# C172-XPNDR-v001.net
KiCad netlist of a schematic drawn in EasyEDA
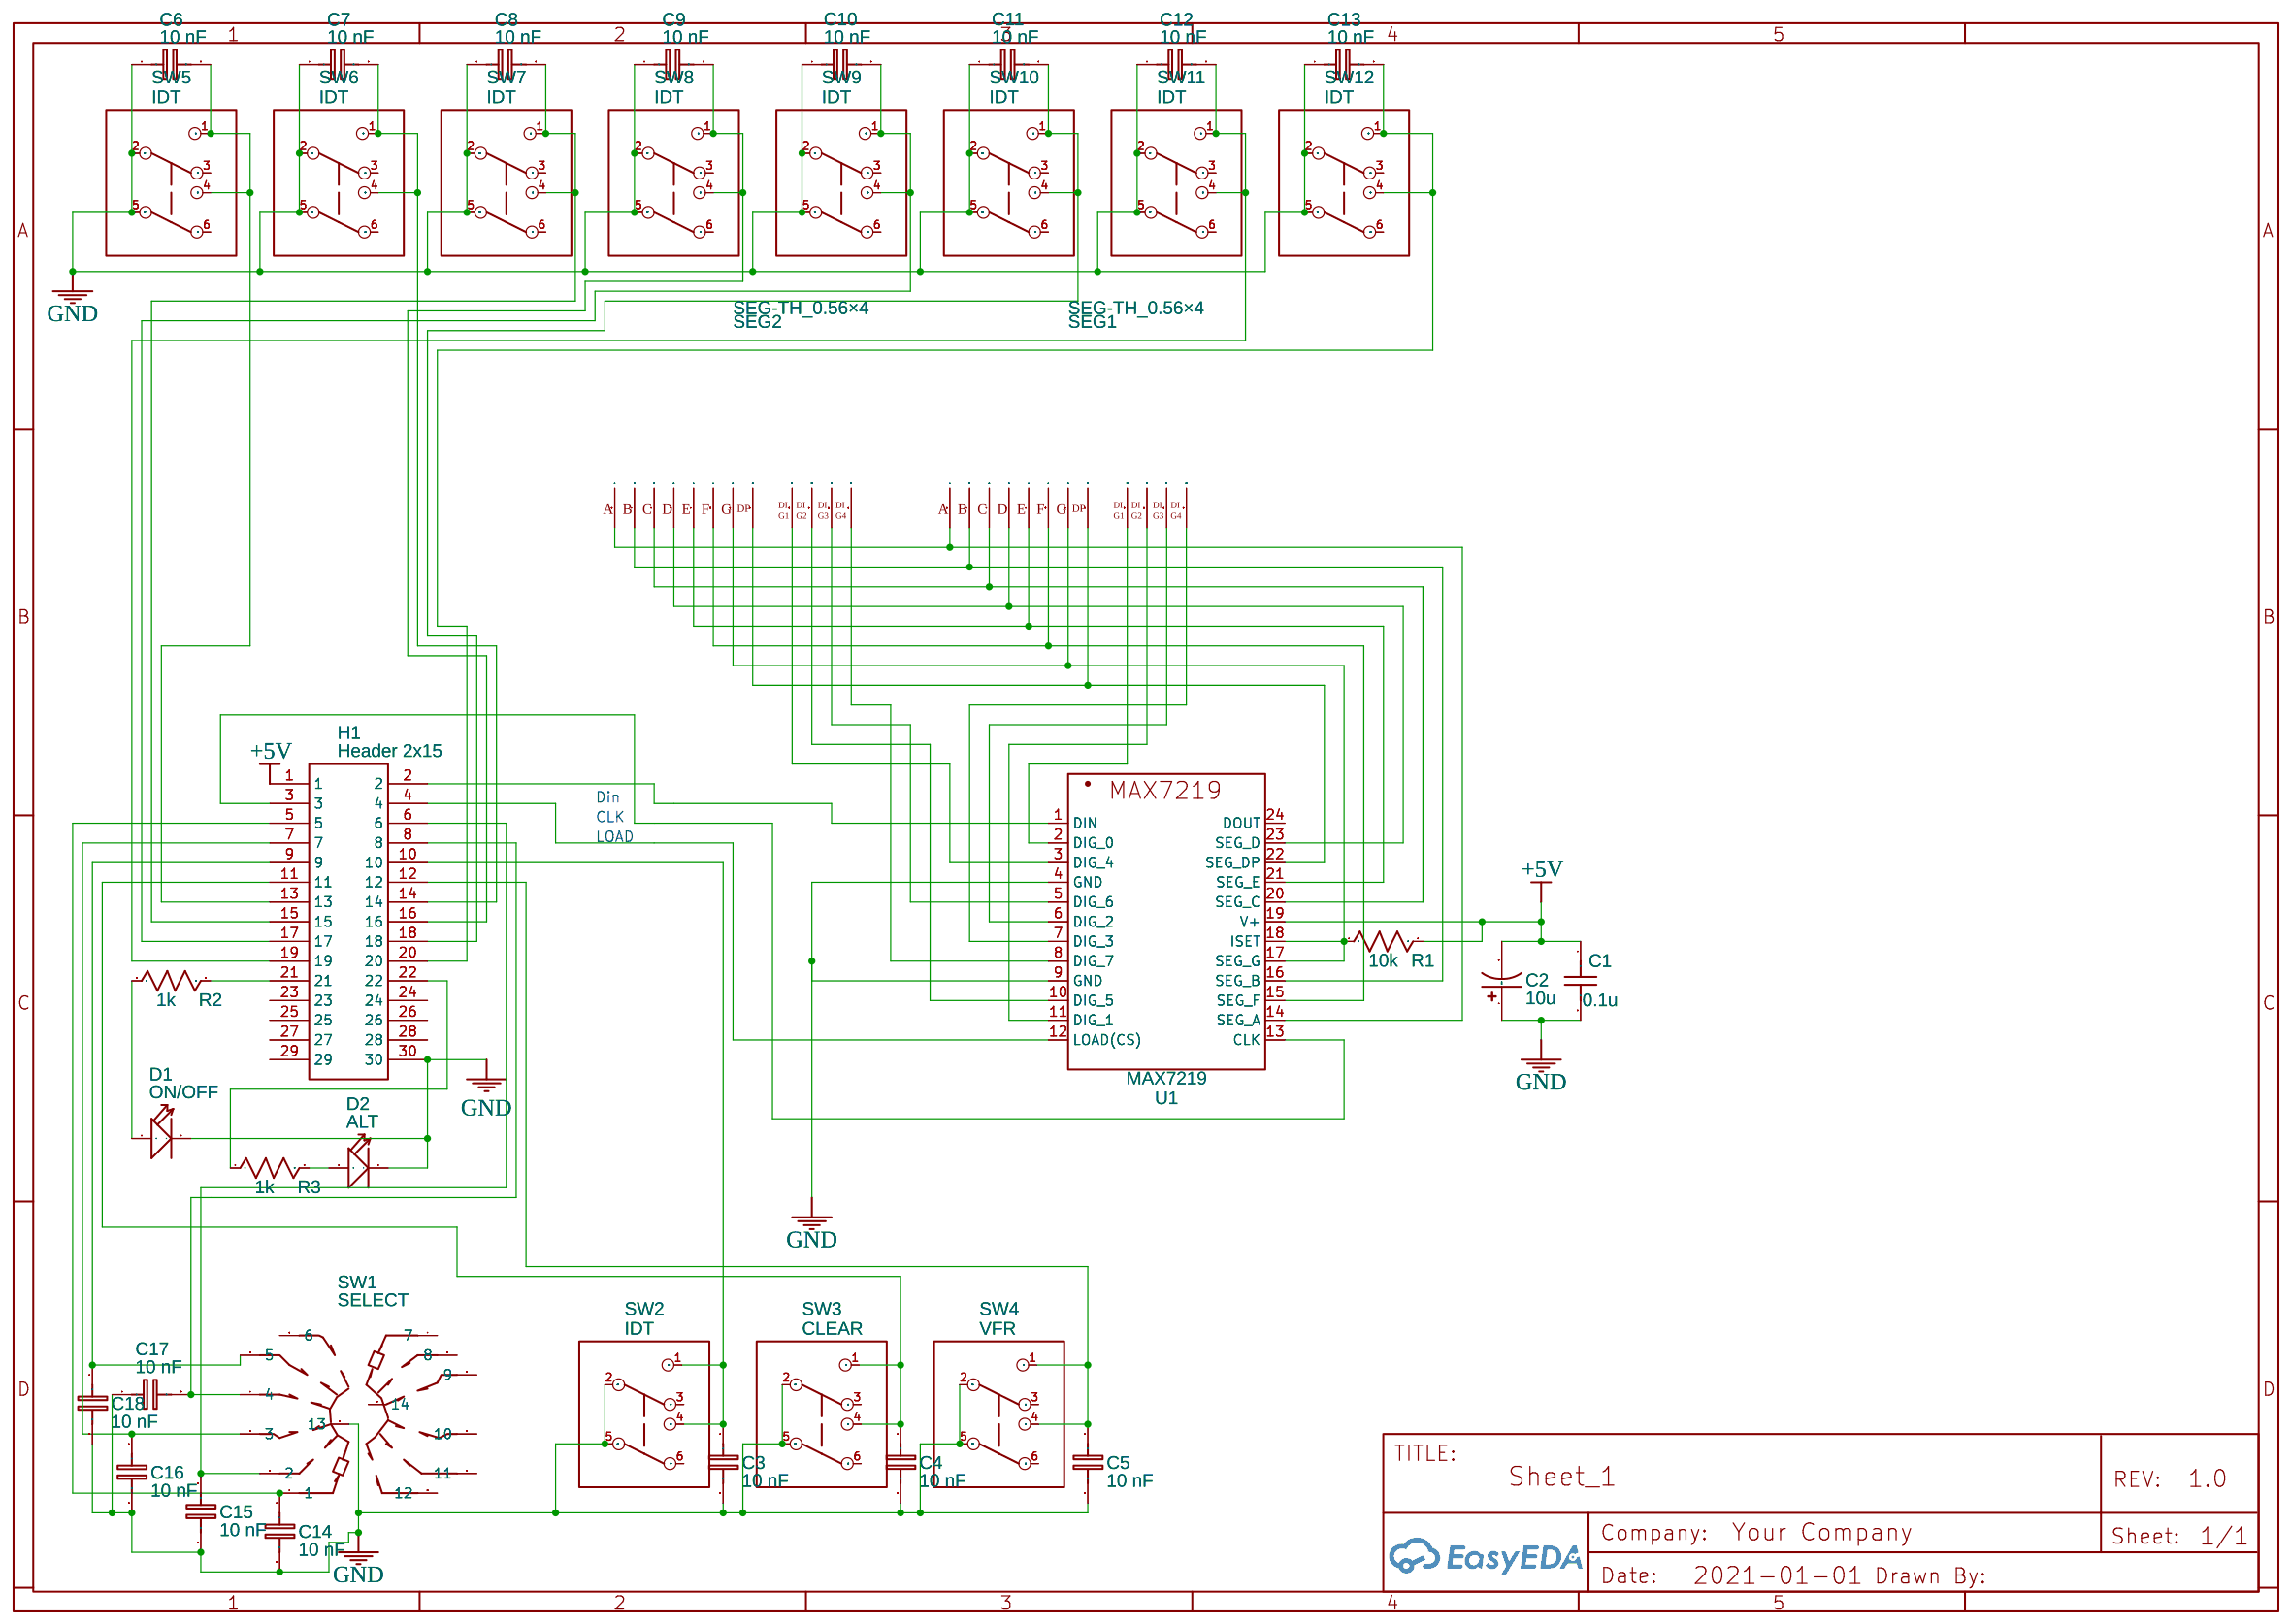
[diagram p0: schematic sheet]

(export (version "E")
  (design (tool "Eeschema 10.0.6"))
  (components
    (comp (ref "C1") (value "0.1u") (libsource (lib "") (part "C_0201_US")))
    (comp (ref "C2") (value "10u") (libsource (lib "") (part "C_Tan_SMD_A_US")))
    (comp (ref "C3") (value "10 nF") (libsource (lib "") (part "Capacitor1_EU_2")))
    (comp (ref "C4") (value "10 nF") (libsource (lib "") (part "Capacitor1_EU_2")))
    (comp (ref "C5") (value "10 nF") (libsource (lib "") (part "Capacitor1_EU")))
    (comp (ref "C6") (value "10 nF") (libsource (lib "") (part "Capacitor1_EU_3")))
    (comp (ref "C7") (value "10 nF") (libsource (lib "") (part "Capacitor1_EU_1")))
    (comp (ref "C8") (value "10 nF") (libsource (lib "") (part "Capacitor1_EU_1")))
    (comp (ref "C9") (value "10 nF") (libsource (lib "") (part "Capacitor1_EU_1")))
    (comp (ref "C10") (value "10 nF") (libsource (lib "") (part "Capacitor1_EU_1")))
    (comp (ref "C11") (value "10 nF") (libsource (lib "") (part "Capacitor1_EU_1")))
    (comp (ref "C12") (value "10 nF") (libsource (lib "") (part "Capacitor1_EU_3")))
    (comp (ref "C13") (value "10 nF") (libsource (lib "") (part "Capacitor1_EU_3")))
    (comp (ref "C14") (value "10 nF") (libsource (lib "") (part "Capacitor1_EU")))
    (comp (ref "C15") (value "10 nF") (libsource (lib "") (part "Capacitor1_EU")))
    (comp (ref "C16") (value "10 nF") (libsource (lib "") (part "Capacitor1_EU")))
    (comp (ref "C17") (value "10 nF") (libsource (lib "") (part "Capacitor1_EU_3")))
    (comp (ref "C18") (value "10 nF") (libsource (lib "") (part "Capacitor1_EU")))
    (comp (ref "D1")
      (value "ON/OFF")
      (fields (field (name "BOM_Manufacturer Part") "?"))
      (libsource (lib "") (part "DIP LED Red-Red;"))
    )
    (comp (ref "D2")
      (value "ALT")
      (fields (field (name "BOM_Manufacturer Part") "?"))
      (libsource (lib "") (part "DIP LED Red-Red;"))
    )
    (comp (ref "H1") (value "Header 2x15") (libsource (lib "") (part "Header 2x15")))
    (comp (ref "R1") (value "10k") (libsource (lib "") (part "R_0201_US")))
    (comp (ref "R2") (value "1k") (libsource (lib "") (part "R_0201_US")))
    (comp (ref "R3") (value "1k") (libsource (lib "") (part "R_0201_US")))
    (comp (ref "SEG1")
      (value "SEG-TH_0.56×4")
      (fields (field (name "BOM_Supplier Part") "C109200"))
      (libsource (lib "") (part "SEG-TH_0.56×4"))
    )
    (comp (ref "SEG2")
      (value "SEG-TH_0.56×4")
      (fields (field (name "BOM_Supplier Part") "C109200"))
      (libsource (lib "") (part "SEG-TH_0.56×4"))
    )
    (comp (ref "SW1")
      (value "SELECT")
      (fields (field (name "BOM_Manufacturer Part") "CK1060"))
      (libsource (lib "") (part "LORLIN  2P6T PCB SW"))
    )
    (comp (ref "SW2") (value "IDT") (libsource (lib "") (part "SW_PUSH_DPDT_MINI_7x7")))
    (comp (ref "SW3") (value "CLEAR") (libsource (lib "") (part "SW_PUSH_DPDT_MINI_7x7")))
    (comp (ref "SW4") (value "VFR") (libsource (lib "") (part "SW_PUSH_DPDT_MINI_7x7")))
    (comp (ref "SW5") (value "IDT") (libsource (lib "") (part "SW_PUSH_DPDT_MINI_7x7")))
    (comp (ref "SW6") (value "IDT") (libsource (lib "") (part "SW_PUSH_DPDT_MINI_7x7")))
    (comp (ref "SW7") (value "IDT") (libsource (lib "") (part "SW_PUSH_DPDT_MINI_7x7")))
    (comp (ref "SW8") (value "IDT") (libsource (lib "") (part "SW_PUSH_DPDT_MINI_7x7")))
    (comp (ref "SW9") (value "IDT") (libsource (lib "") (part "SW_PUSH_DPDT_MINI_7x7")))
    (comp (ref "SW10") (value "IDT") (libsource (lib "") (part "SW_PUSH_DPDT_MINI_7x7")))
    (comp (ref "SW11") (value "IDT") (libsource (lib "") (part "SW_PUSH_DPDT_MINI_7x7")))
    (comp (ref "SW12") (value "IDT") (libsource (lib "") (part "SW_PUSH_DPDT_MINI_7x7")))
    (comp (ref "U1")
      (value "MAX7219")
      (fields (field (name "BOM_Manufacturer Part") "MAXIM") (field (name "BOM_Supplier Part") "C129565"))
      (libsource (lib "") (part "MAX7219"))
    )
  )
  (nets
    (net (code "1") (name "+5V") (class "Default")
      (node (ref "C1") (pin "1") (pinfunction "1_1") (pintype "unspecified"))
      (node (ref "C2") (pin "2") (pinfunction "2_2") (pintype "unspecified"))
      (node (ref "H1") (pin "1") (pinfunction "1_1") (pintype "unspecified"))
      (node (ref "R1") (pin "2") (pinfunction "2_2") (pintype "unspecified"))
      (node (ref "U1") (pin "19") (pinfunction "V+_19") (pintype "unspecified"))
    )
    (net (code "2") (name "GND") (class "Default")
      (node (ref "C1") (pin "2") (pinfunction "2_2") (pintype "unspecified"))
      (node (ref "C10") (pin "1") (pinfunction "1_1") (pintype "unspecified"))
      (node (ref "C11") (pin "1") (pinfunction "1_1") (pintype "unspecified"))
      (node (ref "C12") (pin "1") (pinfunction "1_1") (pintype "unspecified"))
      (node (ref "C13") (pin "1") (pinfunction "1_1") (pintype "unspecified"))
      (node (ref "C14") (pin "2") (pinfunction "2_2") (pintype "unspecified"))
      (node (ref "C15") (pin "2") (pinfunction "2_2") (pintype "unspecified"))
      (node (ref "C16") (pin "2") (pinfunction "2_2") (pintype "unspecified"))
      (node (ref "C17") (pin "1") (pinfunction "1_1") (pintype "unspecified"))
      (node (ref "C18") (pin "2") (pinfunction "2_2") (pintype "unspecified"))
      (node (ref "C2") (pin "1") (pinfunction "1_1") (pintype "unspecified"))
      (node (ref "C3") (pin "2") (pinfunction "2_2") (pintype "unspecified"))
      (node (ref "C4") (pin "2") (pinfunction "2_2") (pintype "unspecified"))
      (node (ref "C5") (pin "2") (pinfunction "2_2") (pintype "unspecified"))
      (node (ref "C6") (pin "1") (pinfunction "1_1") (pintype "unspecified"))
      (node (ref "C7") (pin "1") (pinfunction "1_1") (pintype "unspecified"))
      (node (ref "C8") (pin "1") (pinfunction "1_1") (pintype "unspecified"))
      (node (ref "C9") (pin "1") (pinfunction "1_1") (pintype "unspecified"))
      (node (ref "D1") (pin "K") (pinfunction "-_K") (pintype "unspecified"))
      (node (ref "D2") (pin "K") (pinfunction "-_K") (pintype "unspecified"))
      (node (ref "H1") (pin "30") (pinfunction "30_30") (pintype "unspecified"))
      (node (ref "SW1") (pin "13") (pinfunction "13_13") (pintype "unspecified"))
      (node (ref "SW10") (pin "2") (pinfunction "COM1_2") (pintype "unspecified"))
      (node (ref "SW10") (pin "5") (pinfunction "COM2_5") (pintype "unspecified"))
      (node (ref "SW11") (pin "2") (pinfunction "COM1_2") (pintype "unspecified"))
      (node (ref "SW11") (pin "5") (pinfunction "COM2_5") (pintype "unspecified"))
      (node (ref "SW12") (pin "2") (pinfunction "COM1_2") (pintype "unspecified"))
      (node (ref "SW12") (pin "5") (pinfunction "COM2_5") (pintype "unspecified"))
      (node (ref "SW2") (pin "2") (pinfunction "COM1_2") (pintype "unspecified"))
      (node (ref "SW2") (pin "5") (pinfunction "COM2_5") (pintype "unspecified"))
      (node (ref "SW3") (pin "2") (pinfunction "COM1_2") (pintype "unspecified"))
      (node (ref "SW3") (pin "5") (pinfunction "COM2_5") (pintype "unspecified"))
      (node (ref "SW4") (pin "2") (pinfunction "COM1_2") (pintype "unspecified"))
      (node (ref "SW4") (pin "5") (pinfunction "COM2_5") (pintype "unspecified"))
      (node (ref "SW5") (pin "2") (pinfunction "COM1_2") (pintype "unspecified"))
      (node (ref "SW5") (pin "5") (pinfunction "COM2_5") (pintype "unspecified"))
      (node (ref "SW6") (pin "2") (pinfunction "COM1_2") (pintype "unspecified"))
      (node (ref "SW6") (pin "5") (pinfunction "COM2_5") (pintype "unspecified"))
      (node (ref "SW7") (pin "2") (pinfunction "COM1_2") (pintype "unspecified"))
      (node (ref "SW7") (pin "5") (pinfunction "COM2_5") (pintype "unspecified"))
      (node (ref "SW8") (pin "2") (pinfunction "COM1_2") (pintype "unspecified"))
      (node (ref "SW8") (pin "5") (pinfunction "COM2_5") (pintype "unspecified"))
      (node (ref "SW9") (pin "2") (pinfunction "COM1_2") (pintype "unspecified"))
      (node (ref "SW9") (pin "5") (pinfunction "COM2_5") (pintype "unspecified"))
      (node (ref "U1") (pin "4") (pinfunction "GND_4") (pintype "unspecified"))
      (node (ref "U1") (pin "9") (pinfunction "GND_9") (pintype "unspecified"))
    )
    (net (code "3") (name "Net-(C14-Pad1)") (class "Default")
      (node (ref "C14") (pin "1") (pinfunction "1_1") (pintype "unspecified"))
      (node (ref "H1") (pin "5") (pinfunction "5_5") (pintype "unspecified"))
      (node (ref "SW1") (pin "1") (pinfunction "1_1") (pintype "unspecified"))
    )
    (net (code "4") (name "Net-(C15-Pad1)") (class "Default")
      (node (ref "C15") (pin "1") (pinfunction "1_1") (pintype "unspecified"))
      (node (ref "H1") (pin "6") (pinfunction "6_6") (pintype "unspecified"))
      (node (ref "SW1") (pin "2") (pinfunction "2_2") (pintype "unspecified"))
    )
    (net (code "5") (name "Net-(C16-Pad1)") (class "Default")
      (node (ref "C16") (pin "1") (pinfunction "1_1") (pintype "unspecified"))
      (node (ref "H1") (pin "7") (pinfunction "7_7") (pintype "unspecified"))
      (node (ref "SW1") (pin "3") (pinfunction "3_3") (pintype "unspecified"))
    )
    (net (code "6") (name "Net-(C17-Pad2)") (class "Default")
      (node (ref "C17") (pin "2") (pinfunction "2_2") (pintype "unspecified"))
      (node (ref "H1") (pin "8") (pinfunction "8_8") (pintype "unspecified"))
      (node (ref "SW1") (pin "4") (pinfunction "4_4") (pintype "unspecified"))
    )
    (net (code "7") (name "Net-(C18-Pad1)") (class "Default")
      (node (ref "C18") (pin "1") (pinfunction "1_1") (pintype "unspecified"))
      (node (ref "H1") (pin "9") (pinfunction "9_9") (pintype "unspecified"))
      (node (ref "SW1") (pin "5") (pinfunction "5_5") (pintype "unspecified"))
    )
    (net (code "8") (name "Net-(D1-+)") (class "Default")
      (node (ref "D1") (pin "A") (pinfunction "+_A") (pintype "unspecified"))
      (node (ref "R2") (pin "1") (pinfunction "1_1") (pintype "unspecified"))
    )
    (net (code "9") (name "Net-(D2-+)") (class "Default")
      (node (ref "D2") (pin "A") (pinfunction "+_A") (pintype "unspecified"))
      (node (ref "R3") (pin "2") (pinfunction "2_2") (pintype "unspecified"))
    )
    (net (code "10") (name "Net-(H1-Pad21)") (class "Default")
      (node (ref "H1") (pin "21") (pinfunction "21_21") (pintype "unspecified"))
      (node (ref "R2") (pin "2") (pinfunction "2_2") (pintype "unspecified"))
    )
    (net (code "11") (name "Net-(H1-Pad22)") (class "Default")
      (node (ref "H1") (pin "22") (pinfunction "22_22") (pintype "unspecified"))
      (node (ref "R3") (pin "1") (pinfunction "1_1") (pintype "unspecified"))
    )
    (net (code "12") (name "Net-(SEG1-A)") (class "Default")
      (node (ref "SEG1") (pin "11") (pinfunction "A_11") (pintype "input"))
      (node (ref "SEG2") (pin "11") (pinfunction "A_11") (pintype "input"))
      (node (ref "U1") (pin "14") (pinfunction "SEG_A_14") (pintype "unspecified"))
    )
    (net (code "13") (name "Net-(SEG1-B)") (class "Default")
      (node (ref "SEG1") (pin "7") (pinfunction "B_7") (pintype "input"))
      (node (ref "SEG2") (pin "7") (pinfunction "B_7") (pintype "input"))
      (node (ref "U1") (pin "16") (pinfunction "SEG_B_16") (pintype "unspecified"))
    )
    (net (code "14") (name "Net-(SEG1-C)") (class "Default")
      (node (ref "SEG1") (pin "4") (pinfunction "C_4") (pintype "input"))
      (node (ref "SEG2") (pin "4") (pinfunction "C_4") (pintype "input"))
      (node (ref "U1") (pin "20") (pinfunction "SEG_C_20") (pintype "unspecified"))
    )
    (net (code "15") (name "Net-(SEG1-D)") (class "Default")
      (node (ref "SEG1") (pin "2") (pinfunction "D_2") (pintype "input"))
      (node (ref "SEG2") (pin "2") (pinfunction "D_2") (pintype "input"))
      (node (ref "U1") (pin "23") (pinfunction "SEG_D_23") (pintype "unspecified"))
    )
    (net (code "16") (name "Net-(SEG1-DIG1)") (class "Default")
      (node (ref "SEG1") (pin "12") (pinfunction "DIG1_12") (pintype "input"))
      (node (ref "U1") (pin "2") (pinfunction "DIG_0_2") (pintype "unspecified"))
    )
    (net (code "17") (name "Net-(SEG1-DIG2)") (class "Default")
      (node (ref "SEG1") (pin "9") (pinfunction "DIG2_9") (pintype "input"))
      (node (ref "U1") (pin "11") (pinfunction "DIG_1_11") (pintype "unspecified"))
    )
    (net (code "18") (name "Net-(SEG1-DIG3)") (class "Default")
      (node (ref "SEG1") (pin "8") (pinfunction "DIG3_8") (pintype "input"))
      (node (ref "U1") (pin "6") (pinfunction "DIG_2_6") (pintype "unspecified"))
    )
    (net (code "19") (name "Net-(SEG1-DIG4)") (class "Default")
      (node (ref "SEG1") (pin "6") (pinfunction "DIG4_6") (pintype "input"))
      (node (ref "U1") (pin "7") (pinfunction "DIG_3_7") (pintype "unspecified"))
    )
    (net (code "20") (name "Net-(SEG1-DP)") (class "Default")
      (node (ref "SEG1") (pin "3") (pinfunction "DP_3") (pintype "input"))
      (node (ref "SEG2") (pin "3") (pinfunction "DP_3") (pintype "input"))
      (node (ref "U1") (pin "22") (pinfunction "SEG_DP_22") (pintype "unspecified"))
    )
    (net (code "21") (name "Net-(SEG1-E)") (class "Default")
      (node (ref "SEG1") (pin "1") (pinfunction "E_1") (pintype "input"))
      (node (ref "SEG2") (pin "1") (pinfunction "E_1") (pintype "input"))
      (node (ref "U1") (pin "21") (pinfunction "SEG_E_21") (pintype "unspecified"))
    )
    (net (code "22") (name "Net-(SEG1-F)") (class "Default")
      (node (ref "SEG1") (pin "10") (pinfunction "F_10") (pintype "input"))
      (node (ref "SEG2") (pin "10") (pinfunction "F_10") (pintype "input"))
      (node (ref "U1") (pin "15") (pinfunction "SEG_F_15") (pintype "unspecified"))
    )
    (net (code "23") (name "Net-(SEG1-G)") (class "Default")
      (node (ref "R1") (pin "1") (pinfunction "1_1") (pintype "unspecified"))
      (node (ref "SEG1") (pin "5") (pinfunction "G_5") (pintype "input"))
      (node (ref "SEG2") (pin "5") (pinfunction "G_5") (pintype "input"))
      (node (ref "U1") (pin "17") (pinfunction "SEG_G_17") (pintype "unspecified"))
      (node (ref "U1") (pin "18") (pinfunction "ISET_18") (pintype "unspecified"))
    )
    (net (code "24") (name "Net-(SEG2-DIG1)") (class "Default")
      (node (ref "SEG2") (pin "12") (pinfunction "DIG1_12") (pintype "input"))
      (node (ref "U1") (pin "3") (pinfunction "DIG_4_3") (pintype "unspecified"))
    )
    (net (code "25") (name "Net-(SEG2-DIG2)") (class "Default")
      (node (ref "SEG2") (pin "9") (pinfunction "DIG2_9") (pintype "input"))
      (node (ref "U1") (pin "10") (pinfunction "DIG_5_10") (pintype "unspecified"))
    )
    (net (code "26") (name "Net-(SEG2-DIG3)") (class "Default")
      (node (ref "SEG2") (pin "8") (pinfunction "DIG3_8") (pintype "input"))
      (node (ref "U1") (pin "5") (pinfunction "DIG_6_5") (pintype "unspecified"))
    )
    (net (code "27") (name "Net-(SEG2-DIG4)") (class "Default")
      (node (ref "SEG2") (pin "6") (pinfunction "DIG4_6") (pintype "input"))
      (node (ref "U1") (pin "8") (pinfunction "DIG_7_8") (pintype "unspecified"))
    )
    (net (code "28") (name "Net-(SW2-NO1)") (class "Default")
      (node (ref "C3") (pin "1") (pinfunction "1_1") (pintype "unspecified"))
      (node (ref "H1") (pin "10") (pinfunction "10_10") (pintype "unspecified"))
      (node (ref "SW2") (pin "1") (pinfunction "NO1_1") (pintype "unspecified"))
      (node (ref "SW2") (pin "4") (pinfunction "NO2_4") (pintype "unspecified"))
    )
    (net (code "29") (name "Net-(SW3-NO1)") (class "Default")
      (node (ref "C4") (pin "1") (pinfunction "1_1") (pintype "unspecified"))
      (node (ref "H1") (pin "11") (pinfunction "11_11") (pintype "unspecified"))
      (node (ref "SW3") (pin "1") (pinfunction "NO1_1") (pintype "unspecified"))
      (node (ref "SW3") (pin "4") (pinfunction "NO2_4") (pintype "unspecified"))
    )
    (net (code "30") (name "Net-(SW4-NO1)") (class "Default")
      (node (ref "C5") (pin "1") (pinfunction "1_1") (pintype "unspecified"))
      (node (ref "H1") (pin "12") (pinfunction "12_12") (pintype "unspecified"))
      (node (ref "SW4") (pin "1") (pinfunction "NO1_1") (pintype "unspecified"))
      (node (ref "SW4") (pin "4") (pinfunction "NO2_4") (pintype "unspecified"))
    )
    (net (code "31") (name "Net-(SW5-NO1)") (class "Default")
      (node (ref "C6") (pin "2") (pinfunction "2_2") (pintype "unspecified"))
      (node (ref "H1") (pin "13") (pinfunction "13_13") (pintype "unspecified"))
      (node (ref "SW5") (pin "1") (pinfunction "NO1_1") (pintype "unspecified"))
      (node (ref "SW5") (pin "4") (pinfunction "NO2_4") (pintype "unspecified"))
    )
    (net (code "32") (name "Net-(SW6-NO1)") (class "Default")
      (node (ref "C7") (pin "2") (pinfunction "2_2") (pintype "unspecified"))
      (node (ref "H1") (pin "14") (pinfunction "14_14") (pintype "unspecified"))
      (node (ref "SW6") (pin "1") (pinfunction "NO1_1") (pintype "unspecified"))
      (node (ref "SW6") (pin "4") (pinfunction "NO2_4") (pintype "unspecified"))
    )
    (net (code "33") (name "Net-(SW7-NO1)") (class "Default")
      (node (ref "C8") (pin "2") (pinfunction "2_2") (pintype "unspecified"))
      (node (ref "H1") (pin "15") (pinfunction "15_15") (pintype "unspecified"))
      (node (ref "SW7") (pin "1") (pinfunction "NO1_1") (pintype "unspecified"))
      (node (ref "SW7") (pin "4") (pinfunction "NO2_4") (pintype "unspecified"))
    )
    (net (code "34") (name "Net-(SW8-NO1)") (class "Default")
      (node (ref "C9") (pin "2") (pinfunction "2_2") (pintype "unspecified"))
      (node (ref "H1") (pin "16") (pinfunction "16_16") (pintype "unspecified"))
      (node (ref "SW8") (pin "1") (pinfunction "NO1_1") (pintype "unspecified"))
      (node (ref "SW8") (pin "4") (pinfunction "NO2_4") (pintype "unspecified"))
    )
    (net (code "35") (name "Net-(SW9-NO1)") (class "Default")
      (node (ref "C10") (pin "2") (pinfunction "2_2") (pintype "unspecified"))
      (node (ref "H1") (pin "17") (pinfunction "17_17") (pintype "unspecified"))
      (node (ref "SW9") (pin "1") (pinfunction "NO1_1") (pintype "unspecified"))
      (node (ref "SW9") (pin "4") (pinfunction "NO2_4") (pintype "unspecified"))
    )
    (net (code "36") (name "Net-(SW10-NO1)") (class "Default")
      (node (ref "C11") (pin "2") (pinfunction "2_2") (pintype "unspecified"))
      (node (ref "H1") (pin "18") (pinfunction "18_18") (pintype "unspecified"))
      (node (ref "SW10") (pin "1") (pinfunction "NO1_1") (pintype "unspecified"))
      (node (ref "SW10") (pin "4") (pinfunction "NO2_4") (pintype "unspecified"))
    )
    (net (code "37") (name "Net-(SW11-NO1)") (class "Default")
      (node (ref "C12") (pin "2") (pinfunction "2_2") (pintype "unspecified"))
      (node (ref "H1") (pin "19") (pinfunction "19_19") (pintype "unspecified"))
      (node (ref "SW11") (pin "1") (pinfunction "NO1_1") (pintype "unspecified"))
      (node (ref "SW11") (pin "4") (pinfunction "NO2_4") (pintype "unspecified"))
    )
    (net (code "38") (name "Net-(SW12-NO1)") (class "Default")
      (node (ref "C13") (pin "2") (pinfunction "2_2") (pintype "unspecified"))
      (node (ref "H1") (pin "20") (pinfunction "20_20") (pintype "unspecified"))
      (node (ref "SW12") (pin "1") (pinfunction "NO1_1") (pintype "unspecified"))
      (node (ref "SW12") (pin "4") (pinfunction "NO2_4") (pintype "unspecified"))
    )
    (net (code "39") (name "Net-(U1-CLK)") (class "Default")
      (node (ref "H1") (pin "3") (pinfunction "3_3") (pintype "unspecified"))
      (node (ref "U1") (pin "13") (pinfunction "CLK_13") (pintype "unspecified"))
    )
    (net (code "40") (name "Net-(U1-DIN)") (class "Default")
      (node (ref "H1") (pin "2") (pinfunction "2_2") (pintype "unspecified"))
      (node (ref "U1") (pin "1") (pinfunction "DIN_1") (pintype "unspecified"))
    )
    (net (code "41") (name "Net-(U1-LOAD(CS))") (class "Default")
      (node (ref "H1") (pin "4") (pinfunction "4_4") (pintype "unspecified"))
      (node (ref "U1") (pin "12") (pinfunction "LOAD(CS)_12") (pintype "unspecified"))
    )
    (net (code "42") (name "unconnected-(H1-Pad23)") (class "Default")
      (node (ref "H1") (pin "23") (pinfunction "23_23") (pintype "unspecified"))
    )
    (net (code "43") (name "unconnected-(H1-Pad24)") (class "Default")
      (node (ref "H1") (pin "24") (pinfunction "24_24") (pintype "unspecified"))
    )
    (net (code "44") (name "unconnected-(H1-Pad25)") (class "Default")
      (node (ref "H1") (pin "25") (pinfunction "25_25") (pintype "unspecified"))
    )
    (net (code "45") (name "unconnected-(H1-Pad26)") (class "Default")
      (node (ref "H1") (pin "26") (pinfunction "26_26") (pintype "unspecified"))
    )
    (net (code "46") (name "unconnected-(H1-Pad27)") (class "Default")
      (node (ref "H1") (pin "27") (pinfunction "27_27") (pintype "unspecified"))
    )
    (net (code "47") (name "unconnected-(H1-Pad28)") (class "Default")
      (node (ref "H1") (pin "28") (pinfunction "28_28") (pintype "unspecified"))
    )
    (net (code "48") (name "unconnected-(H1-Pad29)") (class "Default")
      (node (ref "H1") (pin "29") (pinfunction "29_29") (pintype "unspecified"))
    )
    (net (code "49") (name "unconnected-(SW1-Pad6)") (class "Default")
      (node (ref "SW1") (pin "6") (pinfunction "6_6") (pintype "unspecified"))
    )
    (net (code "50") (name "unconnected-(SW1-Pad7)") (class "Default")
      (node (ref "SW1") (pin "7") (pinfunction "7_7") (pintype "unspecified"))
    )
    (net (code "51") (name "unconnected-(SW1-Pad8)") (class "Default")
      (node (ref "SW1") (pin "8") (pinfunction "8_8") (pintype "unspecified"))
    )
    (net (code "52") (name "unconnected-(SW1-Pad9)") (class "Default")
      (node (ref "SW1") (pin "9") (pinfunction "9_9") (pintype "unspecified"))
    )
    (net (code "53") (name "unconnected-(SW1-Pad10)") (class "Default")
      (node (ref "SW1") (pin "10") (pinfunction "10_10") (pintype "unspecified"))
    )
    (net (code "54") (name "unconnected-(SW1-Pad11)") (class "Default")
      (node (ref "SW1") (pin "11") (pinfunction "11_11") (pintype "unspecified"))
    )
    (net (code "55") (name "unconnected-(SW1-Pad12)") (class "Default")
      (node (ref "SW1") (pin "12") (pinfunction "12_12") (pintype "unspecified"))
    )
    (net (code "56") (name "unconnected-(SW1-Pad14)") (class "Default")
      (node (ref "SW1") (pin "14") (pinfunction "14_14") (pintype "unspecified"))
    )
    (net (code "57") (name "unconnected-(SW2-NC1-Pad3)") (class "Default")
      (node (ref "SW2") (pin "3") (pinfunction "NC1_3") (pintype "unspecified"))
    )
    (net (code "58") (name "unconnected-(SW2-NC2-Pad6)") (class "Default")
      (node (ref "SW2") (pin "6") (pinfunction "NC2_6") (pintype "unspecified"))
    )
    (net (code "59") (name "unconnected-(SW3-NC1-Pad3)") (class "Default")
      (node (ref "SW3") (pin "3") (pinfunction "NC1_3") (pintype "unspecified"))
    )
    (net (code "60") (name "unconnected-(SW3-NC2-Pad6)") (class "Default")
      (node (ref "SW3") (pin "6") (pinfunction "NC2_6") (pintype "unspecified"))
    )
    (net (code "61") (name "unconnected-(SW4-NC1-Pad3)") (class "Default")
      (node (ref "SW4") (pin "3") (pinfunction "NC1_3") (pintype "unspecified"))
    )
    (net (code "62") (name "unconnected-(SW4-NC2-Pad6)") (class "Default")
      (node (ref "SW4") (pin "6") (pinfunction "NC2_6") (pintype "unspecified"))
    )
    (net (code "63") (name "unconnected-(SW5-NC1-Pad3)") (class "Default")
      (node (ref "SW5") (pin "3") (pinfunction "NC1_3") (pintype "unspecified"))
    )
    (net (code "64") (name "unconnected-(SW5-NC2-Pad6)") (class "Default")
      (node (ref "SW5") (pin "6") (pinfunction "NC2_6") (pintype "unspecified"))
    )
    (net (code "65") (name "unconnected-(SW6-NC1-Pad3)") (class "Default")
      (node (ref "SW6") (pin "3") (pinfunction "NC1_3") (pintype "unspecified"))
    )
    (net (code "66") (name "unconnected-(SW6-NC2-Pad6)") (class "Default")
      (node (ref "SW6") (pin "6") (pinfunction "NC2_6") (pintype "unspecified"))
    )
    (net (code "67") (name "unconnected-(SW7-NC1-Pad3)") (class "Default")
      (node (ref "SW7") (pin "3") (pinfunction "NC1_3") (pintype "unspecified"))
    )
    (net (code "68") (name "unconnected-(SW7-NC2-Pad6)") (class "Default")
      (node (ref "SW7") (pin "6") (pinfunction "NC2_6") (pintype "unspecified"))
    )
    (net (code "69") (name "unconnected-(SW8-NC1-Pad3)") (class "Default")
      (node (ref "SW8") (pin "3") (pinfunction "NC1_3") (pintype "unspecified"))
    )
    (net (code "70") (name "unconnected-(SW8-NC2-Pad6)") (class "Default")
      (node (ref "SW8") (pin "6") (pinfunction "NC2_6") (pintype "unspecified"))
    )
    (net (code "71") (name "unconnected-(SW9-NC1-Pad3)") (class "Default")
      (node (ref "SW9") (pin "3") (pinfunction "NC1_3") (pintype "unspecified"))
    )
    (net (code "72") (name "unconnected-(SW9-NC2-Pad6)") (class "Default")
      (node (ref "SW9") (pin "6") (pinfunction "NC2_6") (pintype "unspecified"))
    )
    (net (code "73") (name "unconnected-(SW10-NC1-Pad3)") (class "Default")
      (node (ref "SW10") (pin "3") (pinfunction "NC1_3") (pintype "unspecified"))
    )
    (net (code "74") (name "unconnected-(SW10-NC2-Pad6)") (class "Default")
      (node (ref "SW10") (pin "6") (pinfunction "NC2_6") (pintype "unspecified"))
    )
    (net (code "75") (name "unconnected-(SW11-NC1-Pad3)") (class "Default")
      (node (ref "SW11") (pin "3") (pinfunction "NC1_3") (pintype "unspecified"))
    )
    (net (code "76") (name "unconnected-(SW11-NC2-Pad6)") (class "Default")
      (node (ref "SW11") (pin "6") (pinfunction "NC2_6") (pintype "unspecified"))
    )
    (net (code "77") (name "unconnected-(SW12-NC1-Pad3)") (class "Default")
      (node (ref "SW12") (pin "3") (pinfunction "NC1_3") (pintype "unspecified"))
    )
    (net (code "78") (name "unconnected-(SW12-NC2-Pad6)") (class "Default")
      (node (ref "SW12") (pin "6") (pinfunction "NC2_6") (pintype "unspecified"))
    )
    (net (code "79") (name "unconnected-(U1-DOUT-Pad24)") (class "Default")
      (node (ref "U1") (pin "24") (pinfunction "DOUT_24") (pintype "unspecified"))
    )
  )
)
